# 15362.net
KiCad netlist of a schematic drawn in EAGLE
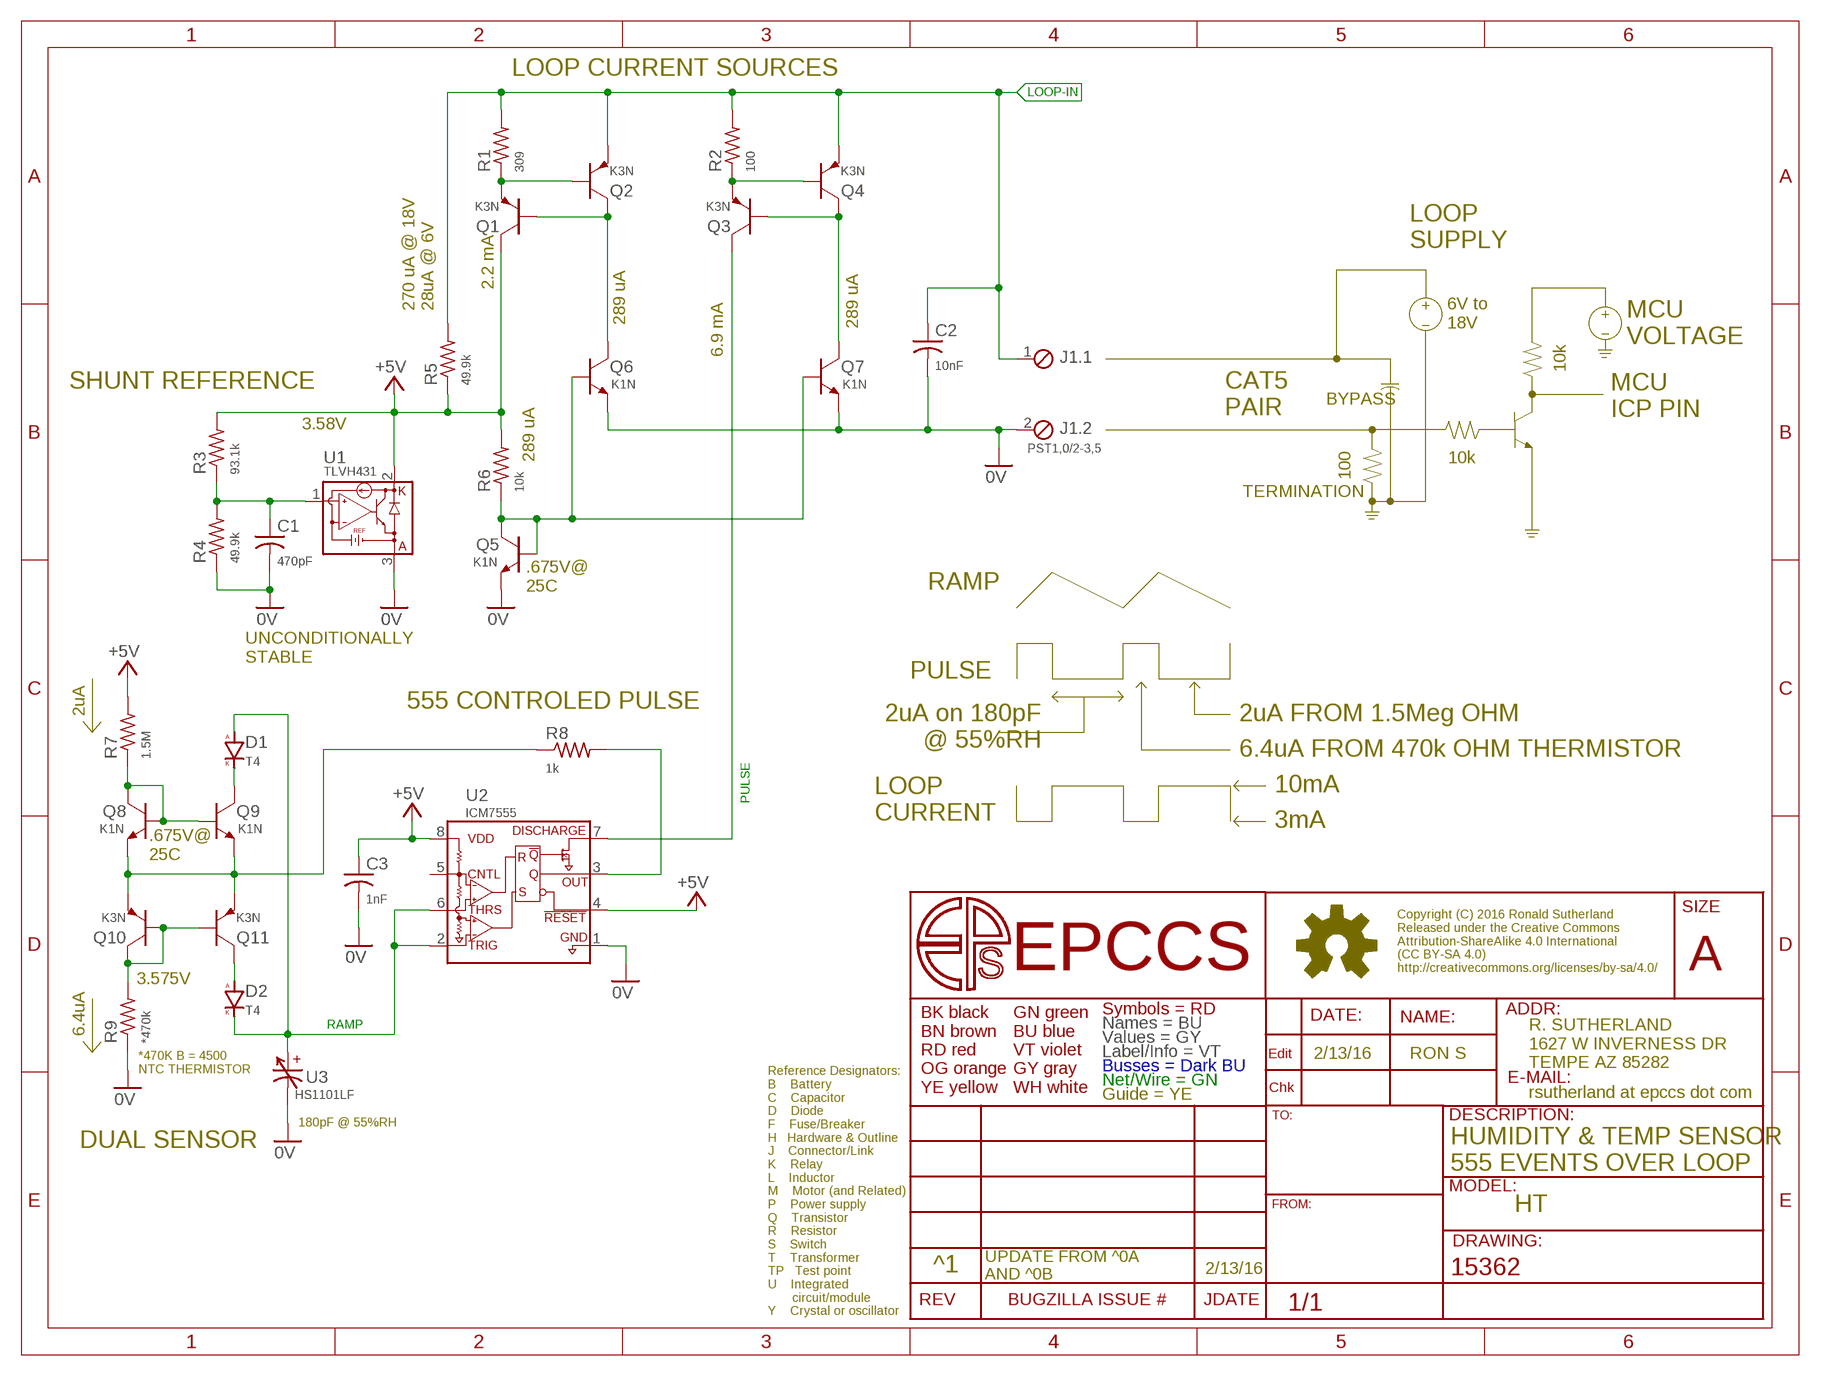
[diagram p0: schematic, sheet 1]

(export (version "E")
  (design (tool "Eeschema 10.0.6"))
  (components
    (comp (ref "C1")
      (value "470pF")
      (footprint "eagle-import:C0603(1608)")
      (libsource (lib "eagle-import") (part "CC0603A"))
    )
    (comp (ref "C2")
      (value "10nF")
      (footprint "eagle-import:C0603(1608)")
      (libsource (lib "eagle-import") (part "CC0603A"))
    )
    (comp (ref "C3")
      (value "1nF")
      (footprint "eagle-import:C0603(1608)")
      (libsource (lib "eagle-import") (part "CC0603A"))
    )
    (comp (ref "D1")
      (value "T4")
      (footprint "eagle-import:SOD123")
      (libsource (lib "eagle-import") (part "DSOD123"))
    )
    (comp (ref "D2")
      (value "T4")
      (footprint "eagle-import:SOD123")
      (libsource (lib "eagle-import") (part "DSOD123"))
    )
    (comp (ref "J1")
      (value "PST1,0/2-3,5")
      (footprint "eagle-import:MCV2")
      (libsource (lib "eagle-import") (part "MCV2"))
    )
    (comp (ref "Q1")
      (value "K3N")
      (footprint "eagle-import:SOT23")
      (libsource (lib "eagle-import") (part "PNPSOT23"))
    )
    (comp (ref "Q2")
      (value "K3N")
      (footprint "eagle-import:SOT23")
      (libsource (lib "eagle-import") (part "PNPSOT23"))
    )
    (comp (ref "Q3")
      (value "K3N")
      (footprint "eagle-import:SOT23")
      (libsource (lib "eagle-import") (part "PNPSOT23"))
    )
    (comp (ref "Q4")
      (value "K3N")
      (footprint "eagle-import:SOT23")
      (libsource (lib "eagle-import") (part "PNPSOT23"))
    )
    (comp (ref "Q5")
      (value "K1N")
      (footprint "eagle-import:SOT23")
      (libsource (lib "eagle-import") (part "NPNSOT23"))
    )
    (comp (ref "Q6")
      (value "K1N")
      (footprint "eagle-import:SOT23")
      (libsource (lib "eagle-import") (part "NPNSOT23"))
    )
    (comp (ref "Q7")
      (value "K1N")
      (footprint "eagle-import:SOT23")
      (libsource (lib "eagle-import") (part "NPNSOT23"))
    )
    (comp (ref "Q8")
      (value "K1N")
      (footprint "eagle-import:SOT23")
      (libsource (lib "eagle-import") (part "NPNSOT23"))
    )
    (comp (ref "Q9")
      (value "K1N")
      (footprint "eagle-import:SOT23")
      (libsource (lib "eagle-import") (part "NPNSOT23"))
    )
    (comp (ref "Q10")
      (value "K3N")
      (footprint "eagle-import:SOT23")
      (libsource (lib "eagle-import") (part "PNPSOT23"))
    )
    (comp (ref "Q11")
      (value "K3N")
      (footprint "eagle-import:SOT23")
      (libsource (lib "eagle-import") (part "PNPSOT23"))
    )
    (comp (ref "R1")
      (value "309")
      (footprint "eagle-import:C0805(2012)")
      (libsource (lib "eagle-import") (part "R0805"))
    )
    (comp (ref "R2")
      (value "100")
      (footprint "eagle-import:C0805(2012)")
      (libsource (lib "eagle-import") (part "R0805"))
    )
    (comp (ref "R3")
      (value "93.1k")
      (footprint "eagle-import:C0805(2012)")
      (libsource (lib "eagle-import") (part "R0805"))
    )
    (comp (ref "R4")
      (value "49.9k")
      (footprint "eagle-import:C0805(2012)")
      (libsource (lib "eagle-import") (part "R0805"))
    )
    (comp (ref "R5")
      (value "49.9k")
      (footprint "eagle-import:C0805(2012)")
      (libsource (lib "eagle-import") (part "R0805"))
    )
    (comp (ref "R6")
      (value "10k")
      (footprint "eagle-import:C0805(2012)")
      (libsource (lib "eagle-import") (part "R0805"))
    )
    (comp (ref "R7")
      (value "1.5M")
      (footprint "eagle-import:C0805(2012)")
      (libsource (lib "eagle-import") (part "R0805"))
    )
    (comp (ref "R8")
      (value "1k")
      (footprint "eagle-import:C0805(2012)")
      (libsource (lib "eagle-import") (part "R0805"))
    )
    (comp (ref "R9")
      (value "*470k")
      (footprint "eagle-import:C0805(2012)")
      (libsource (lib "eagle-import") (part "R0805"))
    )
    (comp (ref "U1")
      (value "TLVH431")
      (footprint "eagle-import:SOT23")
      (libsource (lib "eagle-import") (part "TL432SOT23"))
    )
    (comp (ref "U2")
      (value "ICM7555")
      (footprint "eagle-import:SOIC8")
      (libsource (lib "eagle-import") (part "ICM7555"))
    )
    (comp (ref "U3")
      (value "HS1101LF")
      (footprint "eagle-import:HS1101")
      (libsource (lib "eagle-import") (part "HS1101"))
    )
  )
  (nets
    (net (code "1") (name "+5V") (class "Default")
      (node (ref "C3") (pin "1") (pinfunction "1_1") (pintype "passive"))
      (node (ref "Q1") (pin "C") (pinfunction "C_C") (pintype "passive"))
      (node (ref "R3") (pin "2") (pinfunction "2_2") (pintype "passive"))
      (node (ref "R5") (pin "1") (pinfunction "1_1") (pintype "passive"))
      (node (ref "R6") (pin "2") (pinfunction "2_2") (pintype "passive"))
      (node (ref "R7") (pin "2") (pinfunction "2_2") (pintype "passive"))
      (node (ref "U1") (pin "2") (pinfunction "K_2") (pintype "bidirectional"))
      (node (ref "U2") (pin "4") (pinfunction "~{RESET}_4") (pintype "input"))
      (node (ref "U2") (pin "8") (pinfunction "VDD_8") (pintype "power_in"))
    )
    (net (code "2") (name "/PULSE") (class "Default")
      (node (ref "Q3") (pin "C") (pinfunction "C_C") (pintype "passive"))
      (node (ref "U2") (pin "7") (pinfunction "DISCHARGE_7") (pintype "output"))
    )
    (net (code "3") (name "/RAMP") (class "Default")
      (node (ref "D1") (pin "A") (pinfunction "A_A") (pintype "passive"))
      (node (ref "D2") (pin "C") (pinfunction "K_C") (pintype "passive"))
      (node (ref "U2") (pin "2") (pinfunction "TRIG_2") (pintype "input"))
      (node (ref "U2") (pin "6") (pinfunction "THRS_6") (pintype "input"))
      (node (ref "U3") (pin "1") (pinfunction "1_1") (pintype "passive"))
    )
    (net (code "4") (name "0V") (class "Default")
      (node (ref "C1") (pin "2") (pinfunction "2_2") (pintype "passive"))
      (node (ref "C2") (pin "2") (pinfunction "2_2") (pintype "passive"))
      (node (ref "C3") (pin "2") (pinfunction "2_2") (pintype "passive"))
      (node (ref "J1") (pin "2") (pinfunction "1_2") (pintype "passive"))
      (node (ref "Q5") (pin "E") (pinfunction "E_E") (pintype "passive"))
      (node (ref "Q6") (pin "E") (pinfunction "E_E") (pintype "passive"))
      (node (ref "Q7") (pin "E") (pinfunction "E_E") (pintype "passive"))
      (node (ref "R4") (pin "1") (pinfunction "1_1") (pintype "passive"))
      (node (ref "R9") (pin "1") (pinfunction "1_1") (pintype "passive"))
      (node (ref "U1") (pin "3") (pinfunction "A_3") (pintype "bidirectional"))
      (node (ref "U2") (pin "1") (pinfunction "GND_1") (pintype "power_in"))
      (node (ref "U3") (pin "2") (pinfunction "2_2") (pintype "passive"))
    )
    (net (code "5") (name "LOOP-IN") (class "Default")
      (node (ref "C2") (pin "1") (pinfunction "1_1") (pintype "passive"))
      (node (ref "J1") (pin "1") (pinfunction "1_1") (pintype "passive"))
      (node (ref "Q2") (pin "E") (pinfunction "E_E") (pintype "passive"))
      (node (ref "Q4") (pin "E") (pinfunction "E_E") (pintype "passive"))
      (node (ref "R1") (pin "2") (pinfunction "2_2") (pintype "passive"))
      (node (ref "R2") (pin "2") (pinfunction "2_2") (pintype "passive"))
      (node (ref "R5") (pin "2") (pinfunction "2_2") (pintype "passive"))
    )
    (net (code "6") (name "Net-(D1-K)") (class "Default")
      (node (ref "D1") (pin "C") (pinfunction "K_C") (pintype "passive"))
      (node (ref "Q9") (pin "C") (pinfunction "C_C") (pintype "passive"))
    )
    (net (code "7") (name "Net-(D2-PadA)") (class "Default")
      (node (ref "D2") (pin "A") (pinfunction "A_A") (pintype "passive"))
      (node (ref "Q11") (pin "C") (pinfunction "C_C") (pintype "passive"))
    )
    (net (code "8") (name "Net-(Q1-PadB)") (class "Default")
      (node (ref "Q1") (pin "B") (pinfunction "B_B") (pintype "passive"))
      (node (ref "Q2") (pin "C") (pinfunction "C_C") (pintype "passive"))
      (node (ref "Q6") (pin "C") (pinfunction "C_C") (pintype "passive"))
    )
    (net (code "9") (name "Net-(Q1-PadE)") (class "Default")
      (node (ref "Q1") (pin "E") (pinfunction "E_E") (pintype "passive"))
      (node (ref "Q2") (pin "B") (pinfunction "B_B") (pintype "passive"))
      (node (ref "R1") (pin "1") (pinfunction "1_1") (pintype "passive"))
    )
    (net (code "10") (name "Net-(Q3-PadB)") (class "Default")
      (node (ref "Q3") (pin "B") (pinfunction "B_B") (pintype "passive"))
      (node (ref "Q4") (pin "C") (pinfunction "C_C") (pintype "passive"))
      (node (ref "Q7") (pin "C") (pinfunction "C_C") (pintype "passive"))
    )
    (net (code "11") (name "Net-(Q3-PadE)") (class "Default")
      (node (ref "Q3") (pin "E") (pinfunction "E_E") (pintype "passive"))
      (node (ref "Q4") (pin "B") (pinfunction "B_B") (pintype "passive"))
      (node (ref "R2") (pin "1") (pinfunction "1_1") (pintype "passive"))
    )
    (net (code "12") (name "Net-(Q5-PadB)") (class "Default")
      (node (ref "Q5") (pin "B") (pinfunction "B_B") (pintype "passive"))
      (node (ref "Q5") (pin "C") (pinfunction "C_C") (pintype "passive"))
      (node (ref "Q6") (pin "B") (pinfunction "B_B") (pintype "passive"))
      (node (ref "Q7") (pin "B") (pinfunction "B_B") (pintype "passive"))
      (node (ref "R6") (pin "1") (pinfunction "1_1") (pintype "passive"))
    )
    (net (code "13") (name "Net-(Q8-PadB)") (class "Default")
      (node (ref "Q8") (pin "B") (pinfunction "B_B") (pintype "passive"))
      (node (ref "Q8") (pin "C") (pinfunction "C_C") (pintype "passive"))
      (node (ref "Q9") (pin "B") (pinfunction "B_B") (pintype "passive"))
      (node (ref "R7") (pin "1") (pinfunction "1_1") (pintype "passive"))
    )
    (net (code "14") (name "Net-(Q10-PadB)") (class "Default")
      (node (ref "Q10") (pin "B") (pinfunction "B_B") (pintype "passive"))
      (node (ref "Q10") (pin "C") (pinfunction "C_C") (pintype "passive"))
      (node (ref "Q11") (pin "B") (pinfunction "B_B") (pintype "passive"))
      (node (ref "R9") (pin "2") (pinfunction "2_2") (pintype "passive"))
    )
    (net (code "15") (name "Net-(Q10-PadE)") (class "Default")
      (node (ref "Q10") (pin "E") (pinfunction "E_E") (pintype "passive"))
      (node (ref "Q11") (pin "E") (pinfunction "E_E") (pintype "passive"))
      (node (ref "Q8") (pin "E") (pinfunction "E_E") (pintype "passive"))
      (node (ref "Q9") (pin "E") (pinfunction "E_E") (pintype "passive"))
      (node (ref "R8") (pin "1") (pinfunction "1_1") (pintype "passive"))
    )
    (net (code "16") (name "Net-(U1-REF)") (class "Default")
      (node (ref "C1") (pin "1") (pinfunction "1_1") (pintype "passive"))
      (node (ref "R3") (pin "1") (pinfunction "1_1") (pintype "passive"))
      (node (ref "R4") (pin "2") (pinfunction "2_2") (pintype "passive"))
      (node (ref "U1") (pin "1") (pinfunction "REF_1") (pintype "bidirectional"))
    )
    (net (code "17") (name "Net-(U2-OUT)") (class "Default")
      (node (ref "R8") (pin "2") (pinfunction "2_2") (pintype "passive"))
      (node (ref "U2") (pin "3") (pinfunction "OUT_3") (pintype "output"))
    )
    (net (code "18") (name "unconnected-(U2-CNTL-Pad5)") (class "Default")
      (node (ref "U2") (pin "5") (pinfunction "CNTL_5") (pintype "bidirectional"))
    )
  )
)
